# 07_FLASH_CONTROLLER.net
KiCad netlist of a schematic drawn in Altium Designer
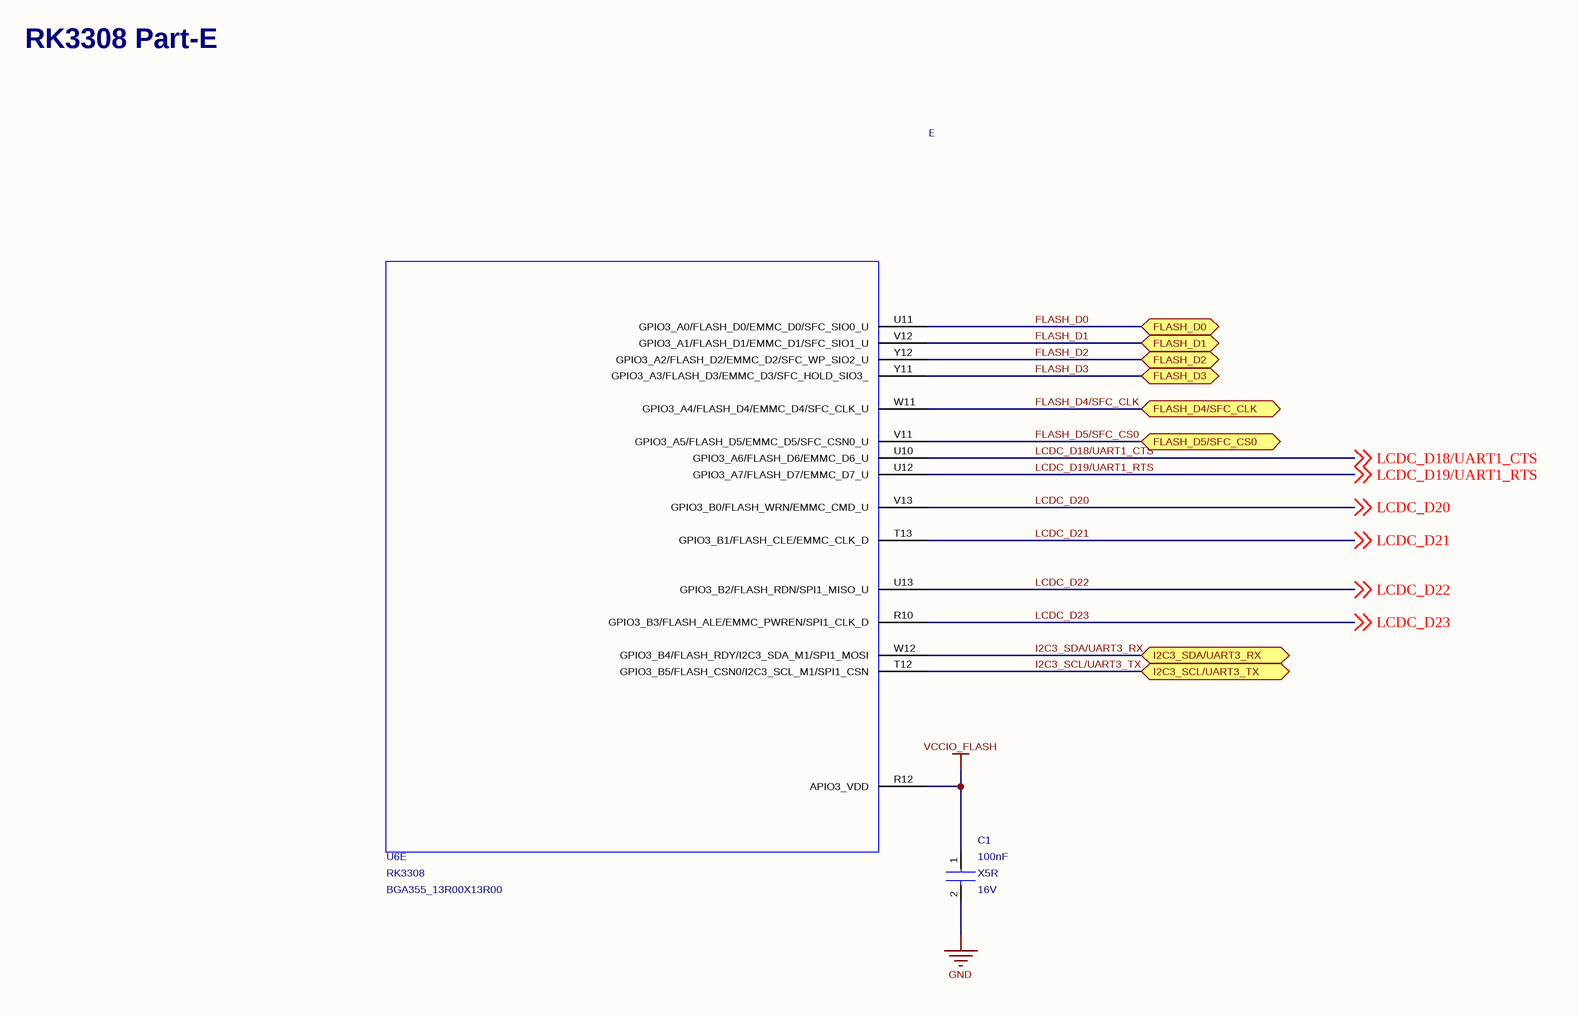
[diagram p0: 07_FLASH_CONTROLLER.SchDoc]

(export (version "E")
  (design (tool "Eeschema 10.0.6"))
  (components
    (comp (ref "C1")
      (value "100nF")
      (footprint "C0402")
      (description "cap,100.00nF,+/-10%,16V,X5R,C0402")
      (fields
        (field (name "DIELECTRIC") "X5R")
        (field (name "VOLTAGE") "16V")
        (field (name "TOLERANCE") "10%")
        (field (name "MANUFACTURER") "TDK")
        (field (name "CREATED_BY") "JJJ")
      )
      (libsource (lib "*") (part "CAP_NP_2"))
    )
    (comp (ref "U6")
      (value "RK3308")
      (footprint "BGA355_13R00X13R00")
      (fields (field (name "PCB DECAL") "BGA355_13R00X13R00") (field (name "MANUFACTURER") "ROCKCHIP"))
      (libsource (lib "*") (part "RK3308"))
    )
  )
  (nets
    (net (code "1") (name "/FLASH_D0") (class "Default")
      (node (ref "U6") (pin "U11") (pinfunction "GPIO3_A0/FLASH_D0/EMMC_D0/SFC_SIO0_U_U11") (pintype "passive"))
    )
    (net (code "2") (name "/FLASH_D1") (class "Default")
      (node (ref "U6") (pin "V12") (pinfunction "GPIO3_A1/FLASH_D1/EMMC_D1/SFC_SIO1_U_V12") (pintype "passive"))
    )
    (net (code "3") (name "/FLASH_D2") (class "Default")
      (node (ref "U6") (pin "Y12") (pinfunction "GPIO3_A2/FLASH_D2/EMMC_D2/SFC_WP_SIO2_U_Y12") (pintype "passive"))
    )
    (net (code "4") (name "/FLASH_D3") (class "Default")
      (node (ref "U6") (pin "Y11") (pinfunction "GPIO3_A3/FLASH_D3/EMMC_D3/SFC_HOLD_SIO3__Y11") (pintype "passive"))
    )
    (net (code "5") (name "/FLASH_D4{slash}SFC_CLK") (class "Default")
      (node (ref "U6") (pin "W11") (pinfunction "GPIO3_A4/FLASH_D4/EMMC_D4/SFC_CLK_U_W11") (pintype "passive"))
    )
    (net (code "6") (name "/FLASH_D5{slash}SFC_CS0") (class "Default")
      (node (ref "U6") (pin "V11") (pinfunction "GPIO3_A5/FLASH_D5/EMMC_D5/SFC_CSN0_U_V11") (pintype "passive"))
    )
    (net (code "7") (name "/I2C3_SCL{slash}UART3_TX") (class "Default")
      (node (ref "U6") (pin "T12") (pinfunction "GPIO3_B5/FLASH_CSN0/I2C3_SCL_M1/SPI1_CSN_T12") (pintype "passive"))
    )
    (net (code "8") (name "/I2C3_SDA{slash}UART3_RX") (class "Default")
      (node (ref "U6") (pin "W12") (pinfunction "GPIO3_B4/FLASH_RDY/I2C3_SDA_M1/SPI1_MOSI_W12") (pintype "passive"))
    )
    (net (code "9") (name "GND") (class "Default")
      (node (ref "C1") (pin "2") (pinfunction "2_2") (pintype "passive"))
    )
    (net (code "10") (name "LCDC_D18{slash}UART1_CTS") (class "Default")
      (node (ref "U6") (pin "U10") (pinfunction "GPIO3_A6/FLASH_D6/EMMC_D6_U_U10") (pintype "passive"))
    )
    (net (code "11") (name "LCDC_D19{slash}UART1_RTS") (class "Default")
      (node (ref "U6") (pin "U12") (pinfunction "GPIO3_A7/FLASH_D7/EMMC_D7_U_U12") (pintype "passive"))
    )
    (net (code "12") (name "LCDC_D20") (class "Default")
      (node (ref "U6") (pin "V13") (pinfunction "GPIO3_B0/FLASH_WRN/EMMC_CMD_U_V13") (pintype "passive"))
    )
    (net (code "13") (name "LCDC_D21") (class "Default")
      (node (ref "U6") (pin "T13") (pinfunction "GPIO3_B1/FLASH_CLE/EMMC_CLK_D_T13") (pintype "passive"))
    )
    (net (code "14") (name "LCDC_D22") (class "Default")
      (node (ref "U6") (pin "U13") (pinfunction "GPIO3_B2/FLASH_RDN/SPI1_MISO_U_U13") (pintype "passive"))
    )
    (net (code "15") (name "LCDC_D23") (class "Default")
      (node (ref "U6") (pin "R10") (pinfunction "GPIO3_B3/FLASH_ALE/EMMC_PWREN/SPI1_CLK_D_R10") (pintype "passive"))
    )
    (net (code "16") (name "VCCIO_FLASH") (class "Default")
      (node (ref "C1") (pin "1") (pinfunction "1_1") (pintype "passive"))
      (node (ref "U6") (pin "R12") (pinfunction "APIO3_VDD_R12") (pintype "passive"))
    )
  )
)
